# Custom_ST-Link_V2_1.net
KiCad netlist of a schematic drawn in Altium Designer
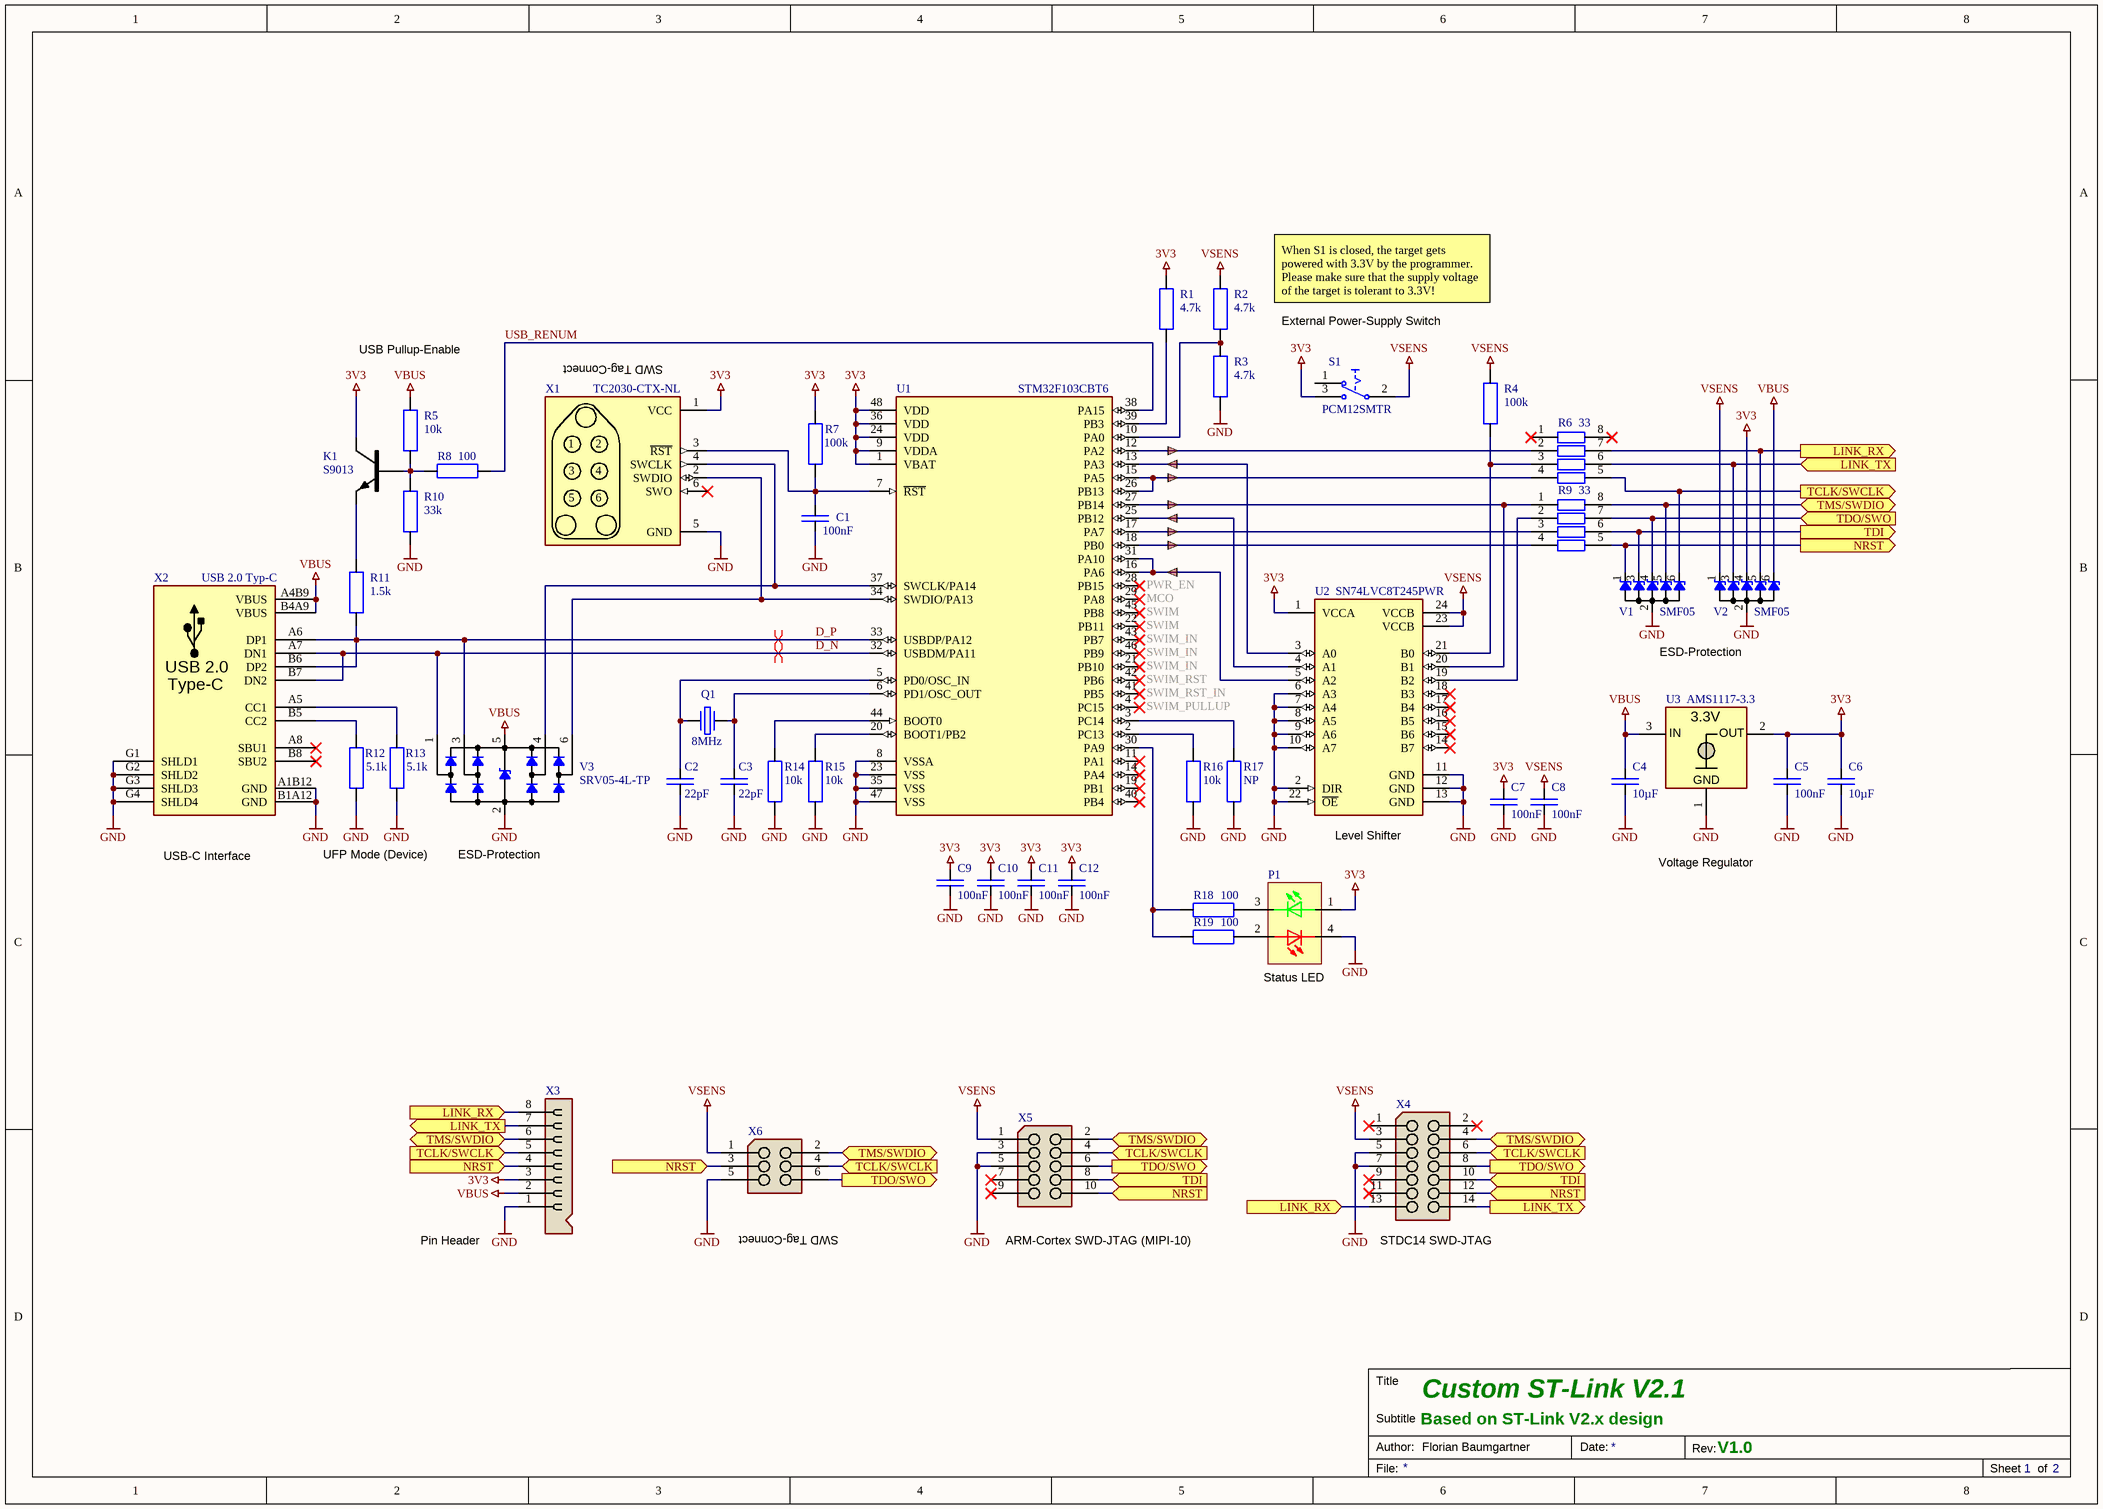
[diagram p0: Custom ST-Link V2.1.SchDoc]

(export (version "E")
  (design (tool "Eeschema 10.0.6"))
  (components
    (comp (ref "C1")
      (value "100nF")
      (footprint "SMD Keramikkondensator 0402")
      (description "CAP-MK")
      (libsource (lib "AudioAmp") (part "C-CAPACITOR"))
    )
    (comp (ref "C2")
      (value "22pF")
      (footprint "SMD Keramikkondensator 0402")
      (description "CAP-MK")
      (libsource (lib "AudioAmp") (part "C-CAPACITOR"))
    )
    (comp (ref "C3")
      (value "22pF")
      (footprint "SMD Keramikkondensator 0402")
      (description "CAP-MK")
      (libsource (lib "AudioAmp") (part "C-CAPACITOR"))
    )
    (comp (ref "C4")
      (value "10µF")
      (footprint "SMD Keramikkondensator 0603")
      (description "CAP-MK")
      (libsource (lib "AudioAmp") (part "C-CAPACITOR"))
    )
    (comp (ref "C5")
      (value "100nF")
      (footprint "SMD Keramikkondensator 0402")
      (description "CAP-MK")
      (libsource (lib "AudioAmp") (part "C-CAPACITOR"))
    )
    (comp (ref "C6")
      (value "10µF")
      (footprint "SMD Keramikkondensator 0603")
      (description "CAP-MK")
      (libsource (lib "AudioAmp") (part "C-CAPACITOR"))
    )
    (comp (ref "C7")
      (value "100nF")
      (footprint "SMD Keramikkondensator 0402")
      (description "CAP-MK")
      (libsource (lib "AudioAmp") (part "C-CAPACITOR"))
    )
    (comp (ref "C8")
      (value "100nF")
      (footprint "SMD Keramikkondensator 0402")
      (description "CAP-MK")
      (libsource (lib "AudioAmp") (part "C-CAPACITOR"))
    )
    (comp (ref "C9")
      (value "100nF")
      (footprint "SMD Keramikkondensator 0402")
      (description "CAP-MK")
      (libsource (lib "AudioAmp") (part "C-CAPACITOR"))
    )
    (comp (ref "C10")
      (value "100nF")
      (footprint "SMD Keramikkondensator 0402")
      (description "CAP-MK")
      (libsource (lib "AudioAmp") (part "C-CAPACITOR"))
    )
    (comp (ref "C11")
      (value "100nF")
      (footprint "SMD Keramikkondensator 0402")
      (description "CAP-MK")
      (libsource (lib "AudioAmp") (part "C-CAPACITOR"))
    )
    (comp (ref "C12")
      (value "100nF")
      (footprint "SMD Keramikkondensator 0402")
      (description "CAP-MK")
      (libsource (lib "AudioAmp") (part "C-CAPACITOR"))
    )
    (comp (ref "K1")
      (value "S9013")
      (footprint "SMD Transistor SOT-23")
      (description "Transistor NPN (alt V und T)")
      (libsource (lib "TFS Integrated Library") (part "K-BIPT{colon}NPN"))
    )
    (comp (ref "P1")
      (value "LTST-C155KGJRKT")
      (footprint "SMD LED 1210")
      (description "LED Red/Green")
      (libsource (lib "Custom ST-Link") (part "P-LTST-C155KGJRKT"))
    )
    (comp (ref "Q1")
      (value "8MHz")
      (footprint "SMD Crystal 5.0X3.2X1.8")
      (description "Crystal with Shielding")
      (libsource (lib "Custom ST-Link Old") (part "B-QUARZ"))
    )
    (comp (ref "R1")
      (value "4.7k")
      (footprint "SMD Widerstand 0402")
      (description "SMD-Widerstand 1/4W")
      (libsource (lib "Backplane_1") (part "R-RESISTOR"))
    )
    (comp (ref "R2")
      (value "4.7k")
      (footprint "SMD Widerstand 0402")
      (description "SMD-Widerstand 1/4W")
      (libsource (lib "Backplane_1") (part "R-RESISTOR"))
    )
    (comp (ref "R3")
      (value "4.7k")
      (footprint "SMD Widerstand 0402")
      (description "SMD-Widerstand 1/4W")
      (libsource (lib "Backplane_1") (part "R-RESISTOR"))
    )
    (comp (ref "R4")
      (value "100k")
      (footprint "SMD Widerstand 0402")
      (description "RES (E=Heizwiderstand B=Messwandler)")
      (libsource (lib "TFS Integrated Library") (part "R-RESISTOR"))
    )
    (comp (ref "R5")
      (value "10k")
      (footprint "SMD Widerstand 0402")
      (description "RES (E=Heizwiderstand B=Messwandler)")
      (libsource (lib "TFS Integrated Library") (part "R-RESISTOR"))
    )
    (comp (ref "R6")
      (value "33")
      (footprint "SMD Widerstand Array 4-Fach 0402")
      (description "Isolated Resistor Array")
      (libsource (lib "Custom ST-Link Old") (part "R-Array Single (4-Fach)"))
    )
    (comp (ref "R7")
      (value "100k")
      (footprint "SMD Widerstand 0402")
      (description "RES (E=Heizwiderstand B=Messwandler)")
      (libsource (lib "TFS Integrated Library") (part "R-RESISTOR"))
    )
    (comp (ref "R8")
      (value "100")
      (footprint "SMD Widerstand 0402")
      (description "SMD-Widerstand 1/4W")
      (libsource (lib "Backplane_1") (part "R-RESISTOR"))
    )
    (comp (ref "R9")
      (value "33")
      (footprint "SMD Widerstand Array 4-Fach 0402")
      (description "Isolated Resistor Array")
      (libsource (lib "Custom ST-Link Old") (part "R-Array Single (4-Fach)"))
    )
    (comp (ref "R10")
      (value "33k")
      (footprint "SMD Widerstand 0402")
      (description "RES (E=Heizwiderstand B=Messwandler)")
      (libsource (lib "TFS Integrated Library") (part "R-RESISTOR"))
    )
    (comp (ref "R11")
      (value "1.5k")
      (footprint "SMD Widerstand 0402")
      (description "RES (E=Heizwiderstand B=Messwandler)")
      (libsource (lib "TFS Integrated Library") (part "R-RESISTOR"))
    )
    (comp (ref "R12")
      (value "5.1k")
      (footprint "SMD Widerstand 0402")
      (description "SMD-Widerstand 1/4W")
      (libsource (lib "Backplane_1") (part "R-RESISTOR"))
    )
    (comp (ref "R13")
      (value "5.1k")
      (footprint "SMD Widerstand 0402")
      (description "SMD-Widerstand 1/4W")
      (libsource (lib "Backplane_1") (part "R-RESISTOR"))
    )
    (comp (ref "R14")
      (value "10k")
      (footprint "SMD Widerstand 0402")
      (description "RES (E=Heizwiderstand B=Messwandler)")
      (libsource (lib "TFS Integrated Library") (part "R-RESISTOR"))
    )
    (comp (ref "R15")
      (value "10k")
      (footprint "SMD Widerstand 0402")
      (description "RES (E=Heizwiderstand B=Messwandler)")
      (libsource (lib "TFS Integrated Library") (part "R-RESISTOR"))
    )
    (comp (ref "R16")
      (value "10k")
      (footprint "SMD Widerstand 0402")
      (description "RES (E=Heizwiderstand B=Messwandler)")
      (libsource (lib "TFS Integrated Library") (part "R-RESISTOR"))
    )
    (comp (ref "R17")
      (value "NP")
      (footprint "SMD Widerstand 0402")
      (description "RES (E=Heizwiderstand B=Messwandler)")
      (libsource (lib "TFS Integrated Library") (part "R-RESISTOR"))
    )
    (comp (ref "R18")
      (value "100")
      (footprint "SMD Widerstand 0402")
      (description "SMD-Widerstand 1/4W")
      (libsource (lib "Backplane_1") (part "R-RESISTOR"))
    )
    (comp (ref "R19")
      (value "100")
      (footprint "SMD Widerstand 0402")
      (description "SMD-Widerstand 1/4W")
      (libsource (lib "Backplane_1") (part "R-RESISTOR"))
    )
    (comp (ref "S1")
      (value "PCM12SMTR")
      (footprint "SMD Switch SPDT (PCM12SMTR)")
      (description "Miniature Slide Switch")
      (libsource (lib "Custom ST-Link") (part "S-PCM12SMTR"))
    )
    (comp (ref "U1")
      (value "STM32F103CBT6")
      (footprint "SMD IC LQFP-48")
      (description "ARM Cortex-M3 MCU (72MHz, 128kB, 20kB)")
      (libsource (lib "Custom ST-Link") (part "U-STM32F103CBT6"))
    )
    (comp (ref "U2")
      (value "SN74LVC8T245PWR")
      (footprint "SMD IC TSSOP-24")
      (description "Octal dual supply translating transceiver")
      (libsource (lib "Custom ST-Link") (part "U-SN74LVC8T245PWR"))
    )
    (comp (ref "U3")
      (value "AMS1117-3.3")
      (footprint "SMD IC SOT-223")
      (description "LDO Voltage Regulator")
      (libsource (lib "Custom ST-Link Old") (part "T-AMS1117-3.3"))
    )
    (comp (ref "V1")
      (value "SMF05")
      (footprint "SMD IC SOT-363 (SC-70-6)")
      (description "Suppressor Diode Array")
      (libsource (lib "Custom ST-Link") (part "V-SMF05CT1G"))
    )
    (comp (ref "V2")
      (value "SMF05")
      (footprint "SMD IC SOT-363 (SC-70-6)")
      (description "Suppressor Diode Array")
      (libsource (lib "Custom ST-Link") (part "V-SMF05CT1G"))
    )
    (comp (ref "V3")
      (value "SRV05-4L-TP")
      (footprint "SMD IC SOT-23-6")
      (description "Ultra Low Capacitance TVS Array")
      (libsource (lib "Custom ST-Link") (part "V-SRV05-4L-TP"))
    )
    (comp (ref "X1")
      (value "TC2030-CTX-NL")
      (footprint "SMD Connector TC2030-CTX-NL")
      (description "Tag-Connect for ARM-Cortex (6-Pin)")
      (libsource (lib "ZedBoard-Matrix Adapter") (part "X-TC2030-CTX-NL"))
    )
    (comp (ref "X2")
      (value "USB 2.0 Typ-C")
      (footprint "SMD USB-C Socket (A40-00119)")
      (description "Typ-C")
      (libsource (lib "Custom ST-Link") (part "X-USB-Buchse"))
    )
    (comp (ref "X3")
      (value "Buchsenleiste (8-Fach)")
      (footprint "SMD Buchsenleiste 8-Pol (1x8) 90°")
      (libsource (lib "Custom ST-Link Old") (part "X-Buchsenleiste (8-Fach)"))
    )
    (comp (ref "X4")
      (value "JTAG-Header (STDC14)")
      (footprint "SMD Connector 1.27mm (2x7)")
      (libsource (lib "Custom ST-Link Old") (part "X-JTAG-Header (STDC14)"))
    )
    (comp (ref "X5")
      (value "JTAG-Header (ARM-Cortex)")
      (footprint "SMD Connector 1.27mm (2x5)")
      (libsource (lib "Custom ST-Link Old") (part "X-JTAG-Header (ARM-Cortex)"))
    )
    (comp (ref "X6")
      (value "JTAG-Header (Tag-Connect)")
      (footprint "SMD Flachbandkabel 6-Pol Vertikal")
      (libsource (lib "Custom ST-Link Old") (part "X-JTAG-Header (Tag-Connect)"))
    )
  )
  (nets
    (net (code "1") (name "/D_N") (class "Default")
      (node (ref "U1") (pin "32") (pinfunction "USBDM/PA11_32") (pintype "bidirectional"))
      (node (ref "V3") (pin "1") (pinfunction "K_1") (pintype "passive"))
      (node (ref "X2") (pin "A7") (pinfunction "DN1_A7") (pintype "passive"))
      (node (ref "X2") (pin "B7") (pinfunction "DN2_B7") (pintype "passive"))
    )
    (net (code "2") (name "/D_P") (class "Default")
      (node (ref "R11") (pin "1") (pinfunction "1_1") (pintype "passive"))
      (node (ref "U1") (pin "33") (pinfunction "USBDP/PA12_33") (pintype "bidirectional"))
      (node (ref "V3") (pin "3") (pinfunction "K_3") (pintype "passive"))
      (node (ref "X2") (pin "A6") (pinfunction "DP1_A6") (pintype "passive"))
      (node (ref "X2") (pin "B6") (pinfunction "DP2_B6") (pintype "passive"))
    )
    (net (code "3") (name "/LINK_RX") (class "Default")
      (node (ref "R6") (pin "7") (pinfunction "7_7") (pintype "passive"))
      (node (ref "V2") (pin "5") (pinfunction "K_5") (pintype "passive"))
      (node (ref "X3") (pin "8") (pinfunction "8_8") (pintype "passive"))
      (node (ref "X4") (pin "13") (pinfunction "13_13") (pintype "passive"))
    )
    (net (code "4") (name "/LINK_TX") (class "Default")
      (node (ref "R6") (pin "6") (pinfunction "6_6") (pintype "passive"))
      (node (ref "V2") (pin "3") (pinfunction "K_3") (pintype "passive"))
      (node (ref "X3") (pin "7") (pinfunction "7_7") (pintype "passive"))
      (node (ref "X4") (pin "14") (pinfunction "14_14") (pintype "passive"))
    )
    (net (code "5") (name "/NRST") (class "Default")
      (node (ref "R9") (pin "5") (pinfunction "5_5") (pintype "passive"))
      (node (ref "V1") (pin "1") (pinfunction "K_1") (pintype "passive"))
      (node (ref "X3") (pin "4") (pinfunction "4_4") (pintype "passive"))
      (node (ref "X4") (pin "12") (pinfunction "12_12") (pintype "passive"))
      (node (ref "X5") (pin "10") (pinfunction "10_10") (pintype "passive"))
      (node (ref "X6") (pin "3") (pinfunction "3_3") (pintype "passive"))
    )
    (net (code "6") (name "/TCLK{slash}SWCLK") (class "Default")
      (node (ref "R6") (pin "5") (pinfunction "5_5") (pintype "passive"))
      (node (ref "V1") (pin "6") (pinfunction "K_6") (pintype "passive"))
      (node (ref "X3") (pin "5") (pinfunction "5_5") (pintype "passive"))
      (node (ref "X4") (pin "6") (pinfunction "6_6") (pintype "passive"))
      (node (ref "X5") (pin "4") (pinfunction "4_4") (pintype "passive"))
      (node (ref "X6") (pin "4") (pinfunction "4_4") (pintype "passive"))
    )
    (net (code "7") (name "/TDI") (class "Default")
      (node (ref "R9") (pin "6") (pinfunction "6_6") (pintype "passive"))
      (node (ref "V1") (pin "3") (pinfunction "K_3") (pintype "passive"))
      (node (ref "X4") (pin "10") (pinfunction "10_10") (pintype "passive"))
      (node (ref "X5") (pin "8") (pinfunction "8_8") (pintype "passive"))
    )
    (net (code "8") (name "/TDO{slash}SWO") (class "Default")
      (node (ref "R9") (pin "7") (pinfunction "7_7") (pintype "passive"))
      (node (ref "V1") (pin "4") (pinfunction "K_4") (pintype "passive"))
      (node (ref "X4") (pin "8") (pinfunction "8_8") (pintype "passive"))
      (node (ref "X5") (pin "6") (pinfunction "6_6") (pintype "passive"))
      (node (ref "X6") (pin "6") (pinfunction "6_6") (pintype "passive"))
    )
    (net (code "9") (name "/TMS{slash}SWDIO") (class "Default")
      (node (ref "R9") (pin "8") (pinfunction "8_8") (pintype "passive"))
      (node (ref "V1") (pin "5") (pinfunction "K_5") (pintype "passive"))
      (node (ref "X3") (pin "6") (pinfunction "6_6") (pintype "passive"))
      (node (ref "X4") (pin "4") (pinfunction "4_4") (pintype "passive"))
      (node (ref "X5") (pin "2") (pinfunction "2_2") (pintype "passive"))
      (node (ref "X6") (pin "2") (pinfunction "2_2") (pintype "passive"))
    )
    (net (code "10") (name "/USB_RENUM") (class "Default")
      (node (ref "R8") (pin "2") (pinfunction "2_2") (pintype "passive"))
      (node (ref "U1") (pin "38") (pinfunction "PA15_38") (pintype "bidirectional"))
    )
    (net (code "11") (name "3V3") (class "Default")
      (node (ref "C10") (pin "2") (pinfunction "2_2") (pintype "passive"))
      (node (ref "C11") (pin "2") (pinfunction "2_2") (pintype "passive"))
      (node (ref "C12") (pin "2") (pinfunction "2_2") (pintype "passive"))
      (node (ref "C5") (pin "2") (pinfunction "2_2") (pintype "passive"))
      (node (ref "C6") (pin "2") (pinfunction "2_2") (pintype "passive"))
      (node (ref "C7") (pin "2") (pinfunction "2_2") (pintype "passive"))
      (node (ref "C9") (pin "2") (pinfunction "2_2") (pintype "passive"))
      (node (ref "K1") (pin "C") (pinfunction "C_C") (pintype "passive"))
      (node (ref "P1") (pin "1") (pinfunction "GA_1") (pintype "passive"))
      (node (ref "R1") (pin "2") (pinfunction "2_2") (pintype "passive"))
      (node (ref "R7") (pin "2") (pinfunction "2_2") (pintype "passive"))
      (node (ref "S1") (pin "3") (pinfunction "NO1_3") (pintype "passive"))
      (node (ref "U1") (pin "1") (pinfunction "VBAT_1") (pintype "power_in"))
      (node (ref "U1") (pin "24") (pinfunction "VDD_24") (pintype "power_in"))
      (node (ref "U1") (pin "36") (pinfunction "VDD_36") (pintype "power_in"))
      (node (ref "U1") (pin "48") (pinfunction "VDD_48") (pintype "power_in"))
      (node (ref "U1") (pin "9") (pinfunction "VDDA_9") (pintype "power_in"))
      (node (ref "U2") (pin "1") (pinfunction "VCCA_1") (pintype "power_in"))
      (node (ref "U3") (pin "2") (pinfunction "OUT_2") (pintype "power_in"))
      (node (ref "V2") (pin "4") (pinfunction "K_4") (pintype "passive"))
      (node (ref "X1") (pin "1") (pinfunction "VCC_1") (pintype "power_in"))
      (node (ref "X3") (pin "3") (pinfunction "3_3") (pintype "passive"))
    )
    (net (code "12") (name "GND") (class "Default")
      (node (ref "C1") (pin "1") (pinfunction "1_1") (pintype "passive"))
      (node (ref "C10") (pin "1") (pinfunction "1_1") (pintype "passive"))
      (node (ref "C11") (pin "1") (pinfunction "1_1") (pintype "passive"))
      (node (ref "C12") (pin "1") (pinfunction "1_1") (pintype "passive"))
      (node (ref "C2") (pin "2") (pinfunction "2_2") (pintype "passive"))
      (node (ref "C3") (pin "2") (pinfunction "2_2") (pintype "passive"))
      (node (ref "C4") (pin "1") (pinfunction "1_1") (pintype "passive"))
      (node (ref "C5") (pin "1") (pinfunction "1_1") (pintype "passive"))
      (node (ref "C6") (pin "1") (pinfunction "1_1") (pintype "passive"))
      (node (ref "C7") (pin "1") (pinfunction "1_1") (pintype "passive"))
      (node (ref "C8") (pin "1") (pinfunction "1_1") (pintype "passive"))
      (node (ref "C9") (pin "1") (pinfunction "1_1") (pintype "passive"))
      (node (ref "P1") (pin "4") (pinfunction "RC_4") (pintype "passive"))
      (node (ref "R10") (pin "1") (pinfunction "1_1") (pintype "passive"))
      (node (ref "R12") (pin "1") (pinfunction "1_1") (pintype "passive"))
      (node (ref "R13") (pin "1") (pinfunction "1_1") (pintype "passive"))
      (node (ref "R14") (pin "1") (pinfunction "1_1") (pintype "passive"))
      (node (ref "R15") (pin "1") (pinfunction "1_1") (pintype "passive"))
      (node (ref "R16") (pin "1") (pinfunction "1_1") (pintype "passive"))
      (node (ref "R17") (pin "1") (pinfunction "1_1") (pintype "passive"))
      (node (ref "R3") (pin "1") (pinfunction "1_1") (pintype "passive"))
      (node (ref "U1") (pin "23") (pinfunction "VSS_23") (pintype "power_in"))
      (node (ref "U1") (pin "35") (pinfunction "VSS_35") (pintype "power_in"))
      (node (ref "U1") (pin "47") (pinfunction "VSS_47") (pintype "power_in"))
      (node (ref "U1") (pin "8") (pinfunction "VSSA_8") (pintype "power_in"))
      (node (ref "U2") (pin "10") (pinfunction "A7_10") (pintype "bidirectional"))
      (node (ref "U2") (pin "11") (pinfunction "GND_11") (pintype "power_in"))
      (node (ref "U2") (pin "12") (pinfunction "GND_12") (pintype "power_in"))
      (node (ref "U2") (pin "13") (pinfunction "GND_13") (pintype "power_in"))
      (node (ref "U2") (pin "2") (pinfunction "DIR_2") (pintype "input"))
      (node (ref "U2") (pin "22") (pinfunction "~{OE}_22") (pintype "input"))
      (node (ref "U2") (pin "6") (pinfunction "A3_6") (pintype "bidirectional"))
      (node (ref "U2") (pin "7") (pinfunction "A4_7") (pintype "bidirectional"))
      (node (ref "U2") (pin "8") (pinfunction "A5_8") (pintype "bidirectional"))
      (node (ref "U2") (pin "9") (pinfunction "A6_9") (pintype "bidirectional"))
      (node (ref "U3") (pin "1") (pinfunction "GND_1") (pintype "power_in"))
      (node (ref "V1") (pin "2") (pinfunction "A_2") (pintype "passive"))
      (node (ref "V2") (pin "2") (pinfunction "A_2") (pintype "passive"))
      (node (ref "V3") (pin "2") (pinfunction "A_2") (pintype "passive"))
      (node (ref "X1") (pin "5") (pinfunction "GND_5") (pintype "power_in"))
      (node (ref "X2") (pin "A1B12") (pinfunction "GND_A1B12") (pintype "passive"))
      (node (ref "X2") (pin "B1A12") (pinfunction "GND_B1A12") (pintype "passive"))
      (node (ref "X2") (pin "G1") (pinfunction "SHLD1_G1") (pintype "passive"))
      (node (ref "X2") (pin "G2") (pinfunction "SHLD2_G2") (pintype "passive"))
      (node (ref "X2") (pin "G3") (pinfunction "SHLD3_G3") (pintype "passive"))
      (node (ref "X2") (pin "G4") (pinfunction "SHLD4_G4") (pintype "passive"))
      (node (ref "X3") (pin "1") (pinfunction "1_1") (pintype "passive"))
      (node (ref "X4") (pin "5") (pinfunction "5_5") (pintype "passive"))
      (node (ref "X4") (pin "7") (pinfunction "7_7") (pintype "passive"))
      (node (ref "X5") (pin "3") (pinfunction "3_3") (pintype "passive"))
      (node (ref "X5") (pin "5") (pinfunction "5_5") (pintype "passive"))
      (node (ref "X6") (pin "5") (pinfunction "5_5") (pintype "passive"))
    )
    (net (code "13") (name "Net-(K1-PadB)") (class "Default")
      (node (ref "K1") (pin "B") (pinfunction "B_B") (pintype "passive"))
      (node (ref "R10") (pin "2") (pinfunction "2_2") (pintype "passive"))
      (node (ref "R5") (pin "1") (pinfunction "1_1") (pintype "passive"))
      (node (ref "R8") (pin "1") (pinfunction "1_1") (pintype "passive"))
    )
    (net (code "14") (name "Net-(K1-PadE)") (class "Default")
      (node (ref "K1") (pin "E") (pinfunction "E_E") (pintype "passive"))
      (node (ref "R11") (pin "2") (pinfunction "2_2") (pintype "passive"))
    )
    (net (code "15") (name "Net-(P1-GC)") (class "Default")
      (node (ref "P1") (pin "3") (pinfunction "GC_3") (pintype "passive"))
      (node (ref "R18") (pin "2") (pinfunction "2_2") (pintype "passive"))
    )
    (net (code "16") (name "Net-(P1-RA)") (class "Default")
      (node (ref "P1") (pin "2") (pinfunction "RA_2") (pintype "passive"))
      (node (ref "R19") (pin "2") (pinfunction "2_2") (pintype "passive"))
    )
    (net (code "17") (name "Net-(U1-BOOT0)") (class "Default")
      (node (ref "R14") (pin "2") (pinfunction "2_2") (pintype "passive"))
      (node (ref "U1") (pin "44") (pinfunction "BOOT0_44") (pintype "input"))
    )
    (net (code "18") (name "Net-(U1-BOOT1{slash}PB2)") (class "Default")
      (node (ref "R15") (pin "2") (pinfunction "2_2") (pintype "passive"))
      (node (ref "U1") (pin "20") (pinfunction "BOOT1/PB2_20") (pintype "bidirectional"))
    )
    (net (code "19") (name "Net-(U1-PA0)") (class "Default")
      (node (ref "R2") (pin "1") (pinfunction "1_1") (pintype "passive"))
      (node (ref "R3") (pin "2") (pinfunction "2_2") (pintype "passive"))
      (node (ref "U1") (pin "10") (pinfunction "PA0_10") (pintype "bidirectional"))
    )
    (net (code "20") (name "Net-(U1-PA2)") (class "Default")
      (node (ref "R6") (pin "2") (pinfunction "2_2") (pintype "passive"))
      (node (ref "U1") (pin "12") (pinfunction "PA2_12") (pintype "bidirectional"))
    )
    (net (code "21") (name "Net-(U1-PA3)") (class "Default")
      (node (ref "U1") (pin "13") (pinfunction "PA3_13") (pintype "bidirectional"))
      (node (ref "U2") (pin "3") (pinfunction "A0_3") (pintype "bidirectional"))
    )
    (net (code "22") (name "Net-(U1-PA5)") (class "Default")
      (node (ref "R6") (pin "4") (pinfunction "4_4") (pintype "passive"))
      (node (ref "U1") (pin "15") (pinfunction "PA5_15") (pintype "bidirectional"))
      (node (ref "U1") (pin "26") (pinfunction "PB13_26") (pintype "bidirectional"))
    )
    (net (code "23") (name "Net-(U1-PA7)") (class "Default")
      (node (ref "R9") (pin "3") (pinfunction "3_3") (pintype "passive"))
      (node (ref "U1") (pin "17") (pinfunction "PA7_17") (pintype "bidirectional"))
    )
    (net (code "24") (name "Net-(U1-PA9)") (class "Default")
      (node (ref "R18") (pin "1") (pinfunction "1_1") (pintype "passive"))
      (node (ref "R19") (pin "1") (pinfunction "1_1") (pintype "passive"))
      (node (ref "U1") (pin "30") (pinfunction "PA9_30") (pintype "bidirectional"))
    )
    (net (code "25") (name "Net-(U1-PA10)") (class "Default")
      (node (ref "U1") (pin "16") (pinfunction "PA6_16") (pintype "bidirectional"))
      (node (ref "U1") (pin "31") (pinfunction "PA10_31") (pintype "bidirectional"))
      (node (ref "U2") (pin "5") (pinfunction "A2_5") (pintype "bidirectional"))
    )
    (net (code "26") (name "Net-(U1-PB0)") (class "Default")
      (node (ref "R9") (pin "4") (pinfunction "4_4") (pintype "passive"))
      (node (ref "U1") (pin "18") (pinfunction "PB0_18") (pintype "bidirectional"))
    )
    (net (code "27") (name "Net-(U1-PB3)") (class "Default")
      (node (ref "R1") (pin "1") (pinfunction "1_1") (pintype "passive"))
      (node (ref "U1") (pin "39") (pinfunction "PB3_39") (pintype "bidirectional"))
    )
    (net (code "28") (name "Net-(U1-PB12)") (class "Default")
      (node (ref "U1") (pin "25") (pinfunction "PB12_25") (pintype "bidirectional"))
      (node (ref "U2") (pin "4") (pinfunction "A1_4") (pintype "bidirectional"))
    )
    (net (code "29") (name "Net-(U1-PB14)") (class "Default")
      (node (ref "R9") (pin "1") (pinfunction "1_1") (pintype "passive"))
      (node (ref "U1") (pin "27") (pinfunction "PB14_27") (pintype "bidirectional"))
      (node (ref "U2") (pin "20") (pinfunction "B1_20") (pintype "bidirectional"))
    )
    (net (code "30") (name "Net-(U1-PC13)") (class "Default")
      (node (ref "R16") (pin "2") (pinfunction "2_2") (pintype "passive"))
      (node (ref "U1") (pin "2") (pinfunction "PC13_2") (pintype "bidirectional"))
    )
    (net (code "31") (name "Net-(U1-PC14)") (class "Default")
      (node (ref "R17") (pin "2") (pinfunction "2_2") (pintype "passive"))
      (node (ref "U1") (pin "3") (pinfunction "PC14_3") (pintype "bidirectional"))
    )
    (net (code "32") (name "Net-(U1-PD0{slash}OSC_IN)") (class "Default")
      (node (ref "C2") (pin "1") (pinfunction "1_1") (pintype "passive"))
      (node (ref "Q1") (pin "1") (pinfunction "1_1") (pintype "passive"))
      (node (ref "U1") (pin "5") (pinfunction "PD0/OSC_IN_5") (pintype "bidirectional"))
    )
    (net (code "33") (name "Net-(U1-PD1{slash}OSC_OUT)") (class "Default")
      (node (ref "C3") (pin "1") (pinfunction "1_1") (pintype "passive"))
      (node (ref "Q1") (pin "2") (pinfunction "2_2") (pintype "passive"))
      (node (ref "U1") (pin "6") (pinfunction "PD1/OSC_OUT_6") (pintype "bidirectional"))
    )
    (net (code "34") (name "Net-(U1-SWCLK{slash}PA14)") (class "Default")
      (node (ref "U1") (pin "37") (pinfunction "SWCLK/PA14_37") (pintype "bidirectional"))
      (node (ref "V3") (pin "4") (pinfunction "K_4") (pintype "passive"))
      (node (ref "X1") (pin "4") (pinfunction "SWCLK_4") (pintype "output"))
    )
    (net (code "35") (name "Net-(U1-SWDIO{slash}PA13)") (class "Default")
      (node (ref "U1") (pin "34") (pinfunction "SWDIO/PA13_34") (pintype "bidirectional"))
      (node (ref "V3") (pin "6") (pinfunction "K_6") (pintype "passive"))
      (node (ref "X1") (pin "2") (pinfunction "SWDIO_2") (pintype "bidirectional"))
    )
    (net (code "36") (name "Net-(U1-~{RST})") (class "Default")
      (node (ref "C1") (pin "2") (pinfunction "2_2") (pintype "passive"))
      (node (ref "R7") (pin "1") (pinfunction "1_1") (pintype "passive"))
      (node (ref "U1") (pin "7") (pinfunction "~{RST}_7") (pintype "input"))
      (node (ref "X1") (pin "3") (pinfunction "~{RST}_3") (pintype "output"))
    )
    (net (code "37") (name "Net-(U2-B0)") (class "Default")
      (node (ref "R4") (pin "1") (pinfunction "1_1") (pintype "passive"))
      (node (ref "R6") (pin "3") (pinfunction "3_3") (pintype "passive"))
      (node (ref "U2") (pin "21") (pinfunction "B0_21") (pintype "bidirectional"))
    )
    (net (code "38") (name "Net-(U2-B2)") (class "Default")
      (node (ref "R9") (pin "2") (pinfunction "2_2") (pintype "passive"))
      (node (ref "U2") (pin "19") (pinfunction "B2_19") (pintype "bidirectional"))
    )
    (net (code "39") (name "Net-(X2-CC1)") (class "Default")
      (node (ref "R13") (pin "2") (pinfunction "2_2") (pintype "passive"))
      (node (ref "X2") (pin "A5") (pinfunction "CC1_A5") (pintype "passive"))
    )
    (net (code "40") (name "Net-(X2-CC2)") (class "Default")
      (node (ref "R12") (pin "2") (pinfunction "2_2") (pintype "passive"))
      (node (ref "X2") (pin "B5") (pinfunction "CC2_B5") (pintype "passive"))
    )
    (net (code "41") (name "VBUS") (class "Default")
      (node (ref "C4") (pin "2") (pinfunction "2_2") (pintype "passive"))
      (node (ref "R5") (pin "2") (pinfunction "2_2") (pintype "passive"))
      (node (ref "U3") (pin "3") (pinfunction "IN_3") (pintype "power_in"))
      (node (ref "V2") (pin "6") (pinfunction "K_6") (pintype "passive"))
      (node (ref "V3") (pin "5") (pinfunction "K_5") (pintype "passive"))
      (node (ref "X2") (pin "A4B9") (pinfunction "VBUS_A4B9") (pintype "passive"))
      (node (ref "X2") (pin "B4A9") (pinfunction "VBUS_B4A9") (pintype "passive"))
      (node (ref "X3") (pin "2") (pinfunction "2_2") (pintype "passive"))
    )
    (net (code "42") (name "VSENS") (class "Default")
      (node (ref "C8") (pin "2") (pinfunction "2_2") (pintype "passive"))
      (node (ref "R2") (pin "2") (pinfunction "2_2") (pintype "passive"))
      (node (ref "R4") (pin "2") (pinfunction "2_2") (pintype "passive"))
      (node (ref "S1") (pin "2") (pinfunction "COMMON1_2") (pintype "passive"))
      (node (ref "U2") (pin "23") (pinfunction "VCCB_23") (pintype "power_in"))
      (node (ref "U2") (pin "24") (pinfunction "VCCB_24") (pintype "power_in"))
      (node (ref "V2") (pin "1") (pinfunction "K_1") (pintype "passive"))
      (node (ref "X4") (pin "3") (pinfunction "3_3") (pintype "passive"))
      (node (ref "X5") (pin "1") (pinfunction "1_1") (pintype "passive"))
      (node (ref "X6") (pin "1") (pinfunction "1_1") (pintype "passive"))
    )
    (net (code "43") (name "unconnected-(R6-Pad1)") (class "Default")
      (node (ref "R6") (pin "1") (pinfunction "1_1") (pintype "passive+no_connect"))
    )
    (net (code "44") (name "unconnected-(R6-Pad8)") (class "Default")
      (node (ref "R6") (pin "8") (pinfunction "8_8") (pintype "passive+no_connect"))
    )
    (net (code "45") (name "unconnected-(S1-NC1-Pad1)") (class "Default")
      (node (ref "S1") (pin "1") (pinfunction "NC1_1") (pintype "passive"))
    )
    (net (code "46") (name "unconnected-(U1-PA1-Pad11)") (class "Default")
      (node (ref "U1") (pin "11") (pinfunction "PA1_11") (pintype "bidirectional+no_connect"))
    )
    (net (code "47") (name "unconnected-(U1-PA4-Pad14)") (class "Default")
      (node (ref "U1") (pin "14") (pinfunction "PA4_14") (pintype "bidirectional+no_connect"))
    )
    (net (code "48") (name "unconnected-(U1-PA8-Pad29)") (class "Default")
      (node (ref "U1") (pin "29") (pinfunction "PA8_29") (pintype "bidirectional+no_connect"))
    )
    (net (code "49") (name "unconnected-(U1-PB1-Pad19)") (class "Default")
      (node (ref "U1") (pin "19") (pinfunction "PB1_19") (pintype "bidirectional+no_connect"))
    )
    (net (code "50") (name "unconnected-(U1-PB4-Pad40)") (class "Default")
      (node (ref "U1") (pin "40") (pinfunction "PB4_40") (pintype "bidirectional+no_connect"))
    )
    (net (code "51") (name "unconnected-(U1-PB5-Pad41)") (class "Default")
      (node (ref "U1") (pin "41") (pinfunction "PB5_41") (pintype "bidirectional+no_connect"))
    )
    (net (code "52") (name "unconnected-(U1-PB6-Pad42)") (class "Default")
      (node (ref "U1") (pin "42") (pinfunction "PB6_42") (pintype "bidirectional+no_connect"))
    )
    (net (code "53") (name "unconnected-(U1-PB7-Pad43)") (class "Default")
      (node (ref "U1") (pin "43") (pinfunction "PB7_43") (pintype "bidirectional+no_connect"))
    )
    (net (code "54") (name "unconnected-(U1-PB8-Pad45)") (class "Default")
      (node (ref "U1") (pin "45") (pinfunction "PB8_45") (pintype "bidirectional+no_connect"))
    )
    (net (code "55") (name "unconnected-(U1-PB9-Pad46)") (class "Default")
      (node (ref "U1") (pin "46") (pinfunction "PB9_46") (pintype "bidirectional+no_connect"))
    )
    (net (code "56") (name "unconnected-(U1-PB10-Pad21)") (class "Default")
      (node (ref "U1") (pin "21") (pinfunction "PB10_21") (pintype "bidirectional+no_connect"))
    )
    (net (code "57") (name "unconnected-(U1-PB11-Pad22)") (class "Default")
      (node (ref "U1") (pin "22") (pinfunction "PB11_22") (pintype "bidirectional+no_connect"))
    )
    (net (code "58") (name "unconnected-(U1-PB15-Pad28)") (class "Default")
      (node (ref "U1") (pin "28") (pinfunction "PB15_28") (pintype "bidirectional+no_connect"))
    )
    (net (code "59") (name "unconnected-(U1-PC15-Pad4)") (class "Default")
      (node (ref "U1") (pin "4") (pinfunction "PC15_4") (pintype "bidirectional+no_connect"))
    )
    (net (code "60") (name "unconnected-(U2-B3-Pad18)") (class "Default")
      (node (ref "U2") (pin "18") (pinfunction "B3_18") (pintype "bidirectional+no_connect"))
    )
    (net (code "61") (name "unconnected-(U2-B4-Pad17)") (class "Default")
      (node (ref "U2") (pin "17") (pinfunction "B4_17") (pintype "bidirectional+no_connect"))
    )
    (net (code "62") (name "unconnected-(U2-B5-Pad16)") (class "Default")
      (node (ref "U2") (pin "16") (pinfunction "B5_16") (pintype "bidirectional+no_connect"))
    )
    (net (code "63") (name "unconnected-(U2-B6-Pad15)") (class "Default")
      (node (ref "U2") (pin "15") (pinfunction "B6_15") (pintype "bidirectional+no_connect"))
    )
    (net (code "64") (name "unconnected-(U2-B7-Pad14)") (class "Default")
      (node (ref "U2") (pin "14") (pinfunction "B7_14") (pintype "bidirectional+no_connect"))
    )
    (net (code "65") (name "unconnected-(X1-SWO-Pad6)") (class "Default")
      (node (ref "X1") (pin "6") (pinfunction "SWO_6") (pintype "input+no_connect"))
    )
    (net (code "66") (name "unconnected-(X2-SBU1-PadA8)") (class "Default")
      (node (ref "X2") (pin "A8") (pinfunction "SBU1_A8") (pintype "passive+no_connect"))
    )
    (net (code "67") (name "unconnected-(X2-SBU2-PadB8)") (class "Default")
      (node (ref "X2") (pin "B8") (pinfunction "SBU2_B8") (pintype "passive+no_connect"))
    )
    (net (code "68") (name "unconnected-(X4-Pad1)") (class "Default")
      (node (ref "X4") (pin "1") (pinfunction "1_1") (pintype "passive+no_connect"))
    )
    (net (code "69") (name "unconnected-(X4-Pad2)") (class "Default")
      (node (ref "X4") (pin "2") (pinfunction "2_2") (pintype "passive+no_connect"))
    )
    (net (code "70") (name "unconnected-(X4-Pad9)") (class "Default")
      (node (ref "X4") (pin "9") (pinfunction "9_9") (pintype "passive+no_connect"))
    )
    (net (code "71") (name "unconnected-(X4-Pad11)") (class "Default")
      (node (ref "X4") (pin "11") (pinfunction "11_11") (pintype "passive+no_connect"))
    )
    (net (code "72") (name "unconnected-(X5-Pad7)") (class "Default")
      (node (ref "X5") (pin "7") (pinfunction "7_7") (pintype "passive+no_connect"))
    )
    (net (code "73") (name "unconnected-(X5-Pad9)") (class "Default")
      (node (ref "X5") (pin "9") (pinfunction "9_9") (pintype "passive+no_connect"))
    )
  )
)
